# openSX70_MEROE_V7_20190603.net
KiCad netlist of a schematic drawn in EAGLE
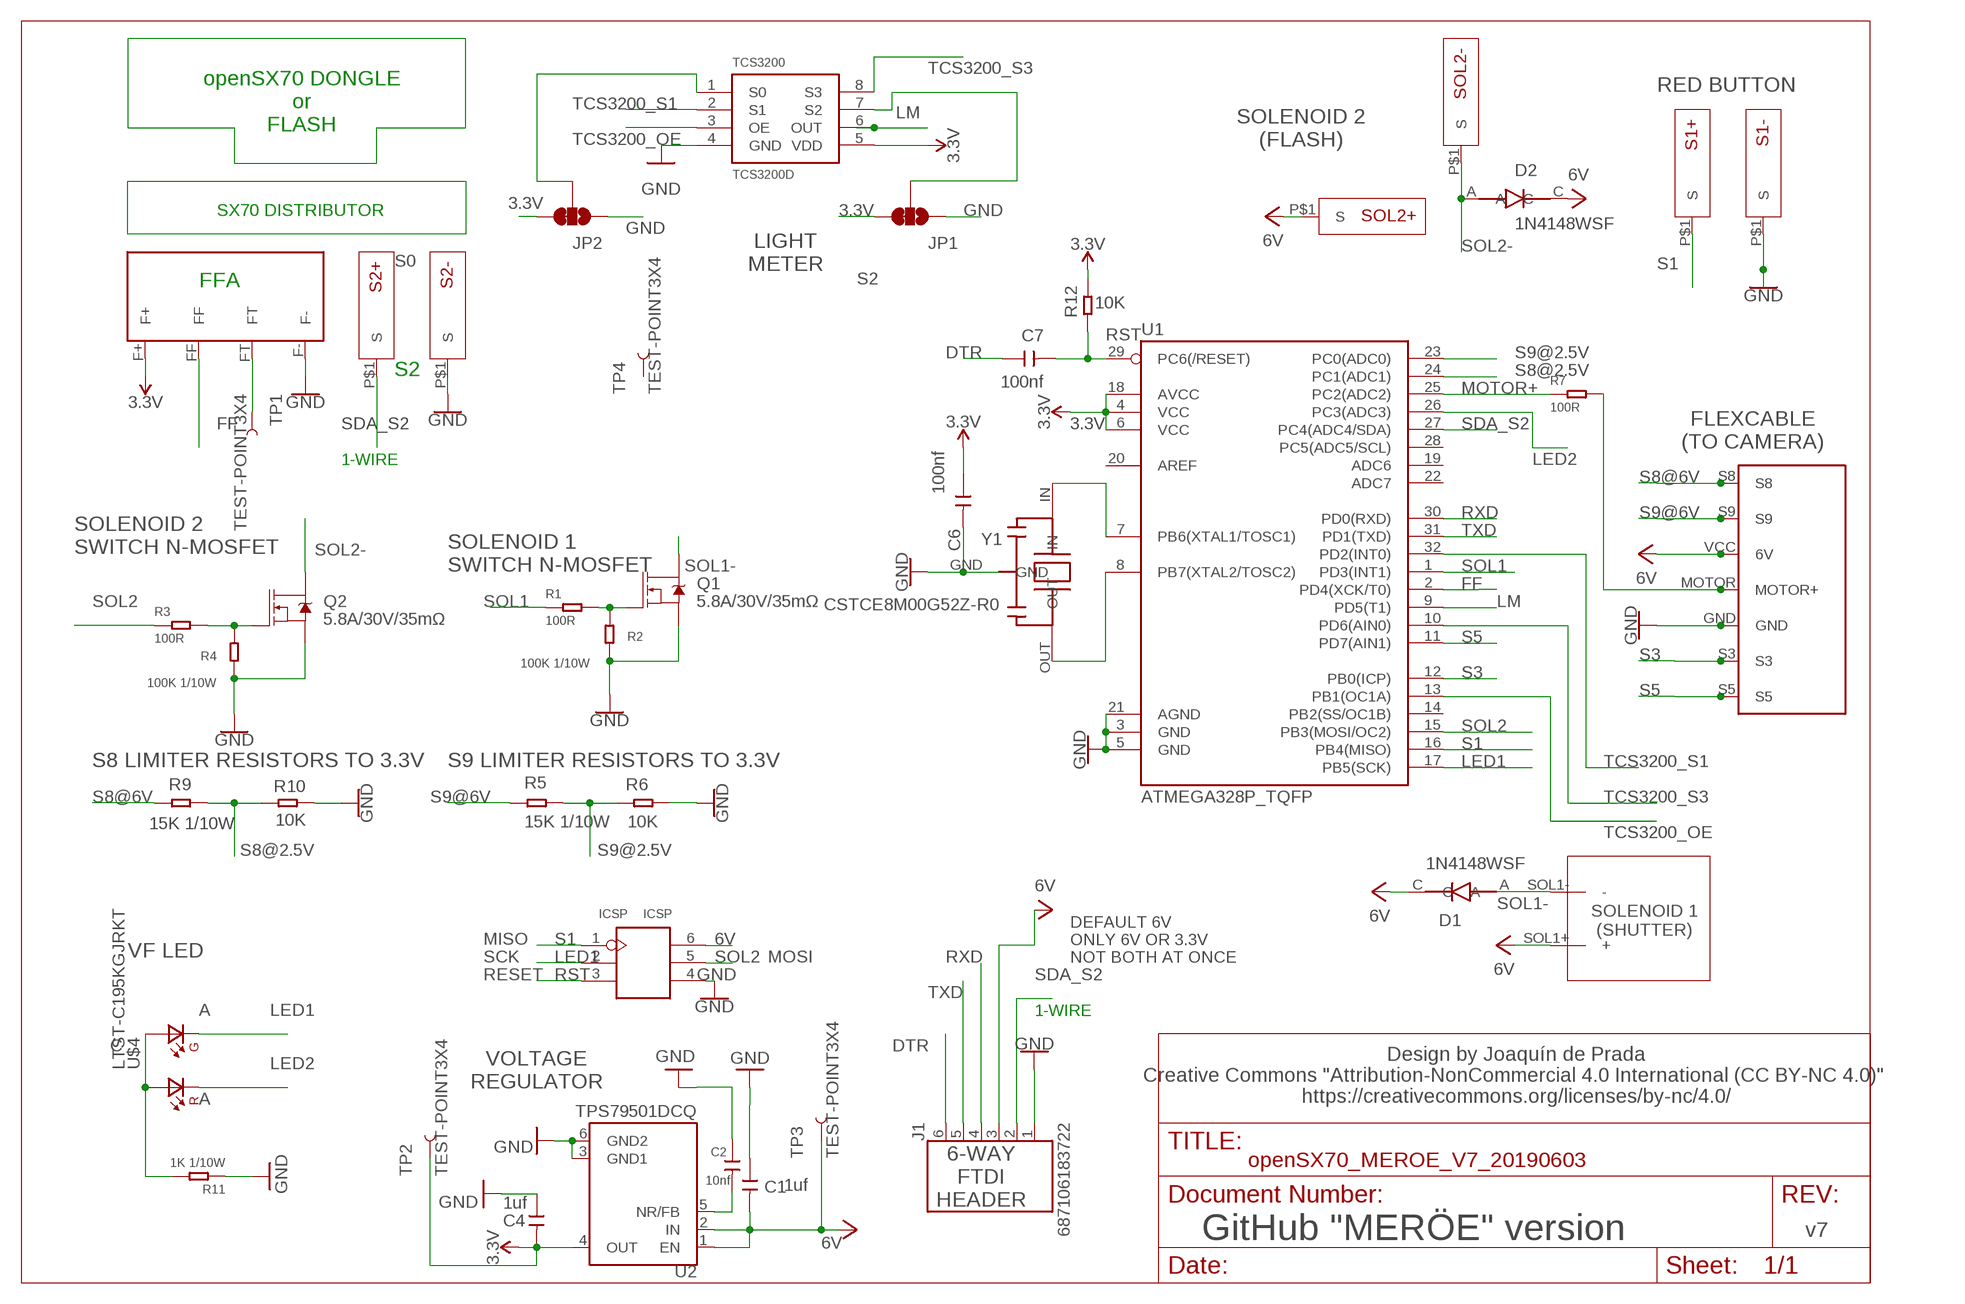
[diagram p0: schematic, sheet 1]

(export (version "E")
  (design (tool "Eeschema 10.0.6"))
  (components
    (comp (ref "C1")
      (value "1uf")
      (footprint "eagle-import:C0603")
      (fields (field (name "MPN") "CC0603KRX5R6BB106"))
      (libsource (lib "eagle-import") (part "CERAMIC-10UF-10V-10%-X5R(0603)"))
    )
    (comp (ref "C2")
      (value "10nf")
      (footprint "eagle-import:C0603")
      (fields (field (name "MPN") "CC0603KRX7R9BB104"))
      (libsource (lib "eagle-import") (part "CERAMIC-100NF-50V-10%-X7R(0603)"))
    )
    (comp (ref "C4")
      (value "1uf")
      (footprint "eagle-import:C0603")
      (fields (field (name "MPN") "CC0603KRX5R6BB106"))
      (libsource (lib "eagle-import") (part "CERAMIC-10UF-10V-10%-X5R(0603)"))
    )
    (comp (ref "C6")
      (value "100nf")
      (footprint "eagle-import:C0603")
      (fields (field (name "MPN") "CC0603KRX7R9BB104"))
      (libsource (lib "eagle-import") (part "CERAMIC-100NF-50V-10%-X7R(0603)"))
    )
    (comp (ref "C7")
      (value "100nf")
      (footprint "eagle-import:C0603")
      (fields (field (name "MPN") "CC0603KRX7R9BB104"))
      (libsource (lib "eagle-import") (part "CERAMIC-100NF-50V-10%-X7R(0603)"))
    )
    (comp (ref "D1")
      (value "1N4148WSF")
      (footprint "eagle-import:SODFL2512X100N")
      (fields (field (name "MANUFACTURER") "Fairchild Semiconductor"))
      (libsource (lib "eagle-import") (part "1N4148WS"))
    )
    (comp (ref "D2")
      (value "1N4148WSF")
      (footprint "eagle-import:SODFL2512X100N")
      (fields (field (name "MANUFACTURER") "Fairchild Semiconductor"))
      (libsource (lib "eagle-import") (part "1N4148WS"))
    )
    (comp (ref "ICSP")
      (value "ICSP")
      (footprint "eagle-import:H2X3-2.54")
      (libsource (lib "eagle-import") (part "ICSP"))
    )
    (comp (ref "J1")
      (value "687106183722")
      (footprint "eagle-import:687106183722")
      (fields (field (name "MF") "Wurth Electronics"))
      (libsource (lib "eagle-import") (part "687106183722"))
    )
    (comp (ref "JP1")
      (value "S2")
      (footprint "eagle-import:SMT-JUMPER_3_1-NC_TRACE_SILK")
      (libsource (lib "eagle-import") (part "JUMPER-SMT_3_1-NC_TRACE_SILK"))
    )
    (comp (ref "JP2")
      (value "S0")
      (footprint "eagle-import:SMT-JUMPER_3_1-NC_TRACE_SILK")
      (libsource (lib "eagle-import") (part "JUMPER-SMT_3_1-NC_TRACE_SILK"))
    )
    (comp (ref "Q1")
      (value "5.8A/30V/35mΩ")
      (footprint "eagle-import:SOT23-3")
      (libsource (lib "eagle-import") (part "MOSFET-NCH-AO3404A"))
    )
    (comp (ref "Q2")
      (value "5.8A/30V/35mΩ")
      (footprint "eagle-import:SOT23-3")
      (libsource (lib "eagle-import") (part "MOSFET-NCH-AO3404A"))
    )
    (comp (ref "R1")
      (value "100R")
      (footprint "eagle-import:R0603")
      (fields (field (name "MPN") "RC0603JR-07100RL"))
      (libsource (lib "eagle-import") (part "SMD-RES-100R-5%-1/10W(0603)"))
    )
    (comp (ref "R2")
      (value "100K 1/10W")
      (footprint "eagle-import:R0603")
      (fields (field (name "MPN") "RC0603JR-07100KL"))
      (libsource (lib "eagle-import") (part "SMD-RES-100K-5%-1/10W(0603)"))
    )
    (comp (ref "R3")
      (value "100R")
      (footprint "eagle-import:R0603")
      (fields (field (name "MPN") "RC0603JR-07100RL"))
      (libsource (lib "eagle-import") (part "SMD-RES-100R-5%-1/10W(0603)"))
    )
    (comp (ref "R4")
      (value "100K 1/10W")
      (footprint "eagle-import:R0603")
      (fields (field (name "MPN") "RC0603JR-07100KL"))
      (libsource (lib "eagle-import") (part "SMD-RES-100K-5%-1/10W(0603)"))
    )
    (comp (ref "R5")
      (value "15K 1/10W")
      (footprint "eagle-import:R0603")
      (fields (field (name "MPN") "RC0603FR-0715KL"))
      (libsource (lib "eagle-import") (part "SMD-RES-15K-1%-1/10W(0603)"))
    )
    (comp (ref "R6")
      (value "10K")
      (footprint "eagle-import:R0603")
      (fields (field (name "MPN") "RC0603FR-0710KL"))
      (libsource (lib "eagle-import") (part "SMD-RES-10K-1%-1/10W(0603)"))
    )
    (comp (ref "R7")
      (value "100R")
      (footprint "eagle-import:R0603")
      (fields (field (name "MPN") "RC0603JR-07100RL"))
      (libsource (lib "eagle-import") (part "SMD-RES-100R-5%-1/10W(0603)"))
    )
    (comp (ref "R9")
      (value "15K 1/10W")
      (footprint "eagle-import:R0603")
      (fields (field (name "MPN") "RC0603FR-0715KL"))
      (libsource (lib "eagle-import") (part "SMD-RES-15K-1%-1/10W(0603)"))
    )
    (comp (ref "R10")
      (value "10K")
      (footprint "eagle-import:R0603")
      (fields (field (name "MPN") "RC0603FR-0710KL"))
      (libsource (lib "eagle-import") (part "SMD-RES-10K-1%-1/10W(0603)"))
    )
    (comp (ref "R11")
      (value "1K 1/10W")
      (footprint "eagle-import:R0603")
      (fields (field (name "MPN") "RC0603JR-071KL"))
      (libsource (lib "eagle-import") (part "SMD-RES-1K-5%-1/10W(0603)"))
    )
    (comp (ref "R12")
      (value "10K")
      (footprint "eagle-import:R0603")
      (fields (field (name "MPN") "RC0603FR-0710KL"))
      (libsource (lib "eagle-import") (part "SMD-RES-10K-1%-1/10W(0603)"))
    )
    (comp (ref "S1+")
      (value "SX70-S-PAD-NEW")
      (footprint "eagle-import:SX70-S-PAD2")
      (libsource (lib "eagle-import") (part "SX70-S-PAD-NEW"))
    )
    (comp (ref "S1-")
      (value "SX70-S-PAD-NEW")
      (footprint "eagle-import:SX70-S-PAD2")
      (libsource (lib "eagle-import") (part "SX70-S-PAD-NEW"))
    )
    (comp (ref "S2+")
      (value "SX70-S-PAD-NEW")
      (footprint "eagle-import:SX70-S-PAD2")
      (libsource (lib "eagle-import") (part "SX70-S-PAD-NEW"))
    )
    (comp (ref "S2-")
      (value "SX70-S-PAD-NEW")
      (footprint "eagle-import:SX70-S-PAD2")
      (libsource (lib "eagle-import") (part "SX70-S-PAD-NEW"))
    )
    (comp (ref "SOL1")
      (value "SX70-SOLENOID1-2PADS")
      (footprint "eagle-import:SX70-SOLENOID1-2")
      (libsource (lib "eagle-import") (part "SX70-SOLENOID1-2PADS"))
    )
    (comp (ref "SOL2+")
      (value "SX70-S-PAD-NEW")
      (footprint "eagle-import:SX70-S-PAD2")
      (libsource (lib "eagle-import") (part "SX70-S-PAD-NEW"))
    )
    (comp (ref "SOL2-")
      (value "SX70-S-PAD-NEW")
      (footprint "eagle-import:SX70-S-PAD2")
      (libsource (lib "eagle-import") (part "SX70-S-PAD-NEW"))
    )
    (comp (ref "TCS3200")
      (value "TCS3200D")
      (footprint "eagle-import:SOIC8")
      (fields (field (name "MF") "ams") (field (name "MP") "TCS3200D-TR"))
      (libsource (lib "eagle-import") (part "TCS3200D"))
    )
    (comp (ref "TP1")
      (value "TEST-POINT3X4")
      (footprint "eagle-import:PAD.03X.04")
      (libsource (lib "eagle-import") (part "TEST-POINT3X4"))
    )
    (comp (ref "TP2")
      (value "TEST-POINT3X4")
      (footprint "eagle-import:PAD.03X.04")
      (libsource (lib "eagle-import") (part "TEST-POINT3X4"))
    )
    (comp (ref "TP3")
      (value "TEST-POINT3X4")
      (footprint "eagle-import:PAD.03X.04")
      (libsource (lib "eagle-import") (part "TEST-POINT3X4"))
    )
    (comp (ref "TP4")
      (value "TEST-POINT3X4")
      (footprint "eagle-import:PAD.03X.04")
      (libsource (lib "eagle-import") (part "TEST-POINT3X4"))
    )
    (comp (ref "U$1")
      (value "SX70-7-PAD")
      (footprint "eagle-import:SX70-7-PAD-PROPER")
      (libsource (lib "eagle-import") (part "SX70-7-PAD"))
    )
    (comp (ref "U$2")
      (value "FFA")
      (footprint "eagle-import:FFA-PAD-PACKAGE")
      (libsource (lib "eagle-import") (part "SX70-FFA-PAD"))
    )
    (comp (ref "U$4")
      (value "LTST-C195KGJRKT")
      (footprint "eagle-import:LTST-BILED-15X16")
      (fields (field (name "MF") "Lite-On Inc."))
      (libsource (lib "eagle-import") (part "LTST-C195KGJRKT"))
    )
    (comp (ref "U1")
      (value "ATMEGA328P_TQFP")
      (footprint "eagle-import:TQFP32-08")
      (libsource (lib "eagle-import") (part "ATMEGA328P_TQFP"))
    )
    (comp (ref "U2")
      (value "TPS79501DCQ")
      (footprint "eagle-import:SOT127P706X180-6N")
      (fields (field (name "MF") "Texas Instruments"))
      (libsource (lib "eagle-import") (part "TPS79501DCQ"))
    )
    (comp (ref "Y1")
      (value "CSTCE8M00G52Z-R0")
      (footprint "eagle-import:CFP95P160X100-3N")
      (fields (field (name "MF") "Murata") (field (name "MP") "CSTCE16M0V53-R0"))
      (libsource (lib "eagle-import") (part "CSTCE16M0V53-R0"))
    )
  )
  (nets
    (net (code "1") (name "/DTR") (class "Default")
      (node (ref "C7") (pin "1") (pinfunction "1_1") (pintype "passive"))
      (node (ref "J1") (pin "6") (pinfunction "1_6") (pintype "passive"))
    )
    (net (code "2") (name "/FF") (class "Default")
      (node (ref "U$2") (pin "FF") (pinfunction "FF_FF") (pintype "bidirectional"))
      (node (ref "U1") (pin "2") (pinfunction "PD4(XCK/T0)_2") (pintype "bidirectional"))
    )
    (net (code "3") (name "/LED1") (class "Default")
      (node (ref "ICSP") (pin "2") (pinfunction "SCK_2") (pintype "bidirectional"))
      (node (ref "U$4") (pin "P$3") (pinfunction "K1_P$3") (pintype "passive"))
      (node (ref "U1") (pin "17") (pinfunction "PB5(SCK)_17") (pintype "bidirectional"))
    )
    (net (code "4") (name "/LED2") (class "Default")
      (node (ref "U$4") (pin "P$4") (pinfunction "K2_P$4") (pintype "passive"))
      (node (ref "U1") (pin "26") (pinfunction "PC3(ADC3)_26") (pintype "bidirectional"))
    )
    (net (code "5") (name "/LM") (class "Default")
      (node (ref "TCS3200") (pin "6") (pinfunction "OUT_6") (pintype "bidirectional"))
      (node (ref "U1") (pin "9") (pinfunction "PD5(T1)_9") (pintype "bidirectional"))
    )
    (net (code "6") (name "/MOTOR+") (class "Default")
      (node (ref "R7") (pin "1") (pinfunction "1_1") (pintype "passive"))
      (node (ref "U1") (pin "25") (pinfunction "PC2(ADC2)_25") (pintype "bidirectional"))
    )
    (net (code "7") (name "/RST") (class "Default")
      (node (ref "C7") (pin "2") (pinfunction "2_2") (pintype "passive"))
      (node (ref "ICSP") (pin "3") (pinfunction "RST_3") (pintype "bidirectional"))
      (node (ref "R12") (pin "1") (pinfunction "1_1") (pintype "passive"))
      (node (ref "U1") (pin "29") (pinfunction "PC6(/RESET)_29") (pintype "bidirectional"))
    )
    (net (code "8") (name "/RXD") (class "Default")
      (node (ref "J1") (pin "4") (pinfunction "3_4") (pintype "passive"))
      (node (ref "U1") (pin "30") (pinfunction "PD0(RXD)_30") (pintype "bidirectional"))
    )
    (net (code "9") (name "/S1") (class "Default")
      (node (ref "ICSP") (pin "1") (pinfunction "MISO_1") (pintype "bidirectional"))
      (node (ref "S1+") (pin "P$1") (pinfunction "S_P$1") (pintype "bidirectional"))
      (node (ref "U1") (pin "16") (pinfunction "PB4(MISO)_16") (pintype "bidirectional"))
    )
    (net (code "10") (name "/S3") (class "Default")
      (node (ref "U$1") (pin "S3") (pinfunction "S3_S3") (pintype "bidirectional"))
      (node (ref "U1") (pin "12") (pinfunction "PB0(ICP)_12") (pintype "bidirectional"))
    )
    (net (code "11") (name "/S5") (class "Default")
      (node (ref "U$1") (pin "S5") (pinfunction "S5_S5") (pintype "bidirectional"))
      (node (ref "U1") (pin "11") (pinfunction "PD7(AIN1)_11") (pintype "bidirectional"))
    )
    (net (code "12") (name "/S8@2.5V") (class "Default")
      (node (ref "R10") (pin "1") (pinfunction "1_1") (pintype "passive"))
      (node (ref "R9") (pin "2") (pinfunction "2_2") (pintype "passive"))
      (node (ref "U1") (pin "24") (pinfunction "PC1(ADC1)_24") (pintype "bidirectional"))
    )
    (net (code "13") (name "/S8@6V") (class "Default")
      (node (ref "R9") (pin "1") (pinfunction "1_1") (pintype "passive"))
      (node (ref "U$1") (pin "S8") (pinfunction "S8_S8") (pintype "bidirectional"))
    )
    (net (code "14") (name "/S9@2.5V") (class "Default")
      (node (ref "R5") (pin "2") (pinfunction "2_2") (pintype "passive"))
      (node (ref "R6") (pin "1") (pinfunction "1_1") (pintype "passive"))
      (node (ref "U1") (pin "23") (pinfunction "PC0(ADC0)_23") (pintype "bidirectional"))
    )
    (net (code "15") (name "/S9@6V") (class "Default")
      (node (ref "R5") (pin "1") (pinfunction "1_1") (pintype "passive"))
      (node (ref "U$1") (pin "S9") (pinfunction "S9_S9") (pintype "bidirectional"))
    )
    (net (code "16") (name "/SDA_S2") (class "Default")
      (node (ref "J1") (pin "2") (pinfunction "5_2") (pintype "passive"))
      (node (ref "S2+") (pin "P$1") (pinfunction "S_P$1") (pintype "bidirectional"))
      (node (ref "U1") (pin "27") (pinfunction "PC4(ADC4/SDA)_27") (pintype "bidirectional"))
    )
    (net (code "17") (name "/SOL1") (class "Default")
      (node (ref "R1") (pin "1") (pinfunction "1_1") (pintype "passive"))
      (node (ref "U1") (pin "1") (pinfunction "PD3(INT1)_1") (pintype "bidirectional"))
    )
    (net (code "18") (name "/SOL1-") (class "Default")
      (node (ref "D1") (pin "A") (pinfunction "A_A") (pintype "passive"))
      (node (ref "Q1") (pin "3") (pinfunction "D_3") (pintype "bidirectional"))
      (node (ref "SOL1") (pin "SOL1-") (pinfunction "-_SOL1-") (pintype "bidirectional"))
    )
    (net (code "19") (name "/SOL2") (class "Default")
      (node (ref "ICSP") (pin "5") (pinfunction "MOSI_5") (pintype "bidirectional"))
      (node (ref "R3") (pin "1") (pinfunction "1_1") (pintype "passive"))
      (node (ref "U1") (pin "15") (pinfunction "PB3(MOSI/OC2)_15") (pintype "bidirectional"))
    )
    (net (code "20") (name "/SOL2-") (class "Default")
      (node (ref "D2") (pin "A") (pinfunction "A_A") (pintype "passive"))
      (node (ref "Q2") (pin "3") (pinfunction "D_3") (pintype "bidirectional"))
      (node (ref "SOL2-") (pin "P$1") (pinfunction "S_P$1") (pintype "bidirectional"))
    )
    (net (code "21") (name "/TCS3200_OE") (class "Default")
      (node (ref "TCS3200") (pin "3") (pinfunction "OE_3") (pintype "bidirectional"))
      (node (ref "U1") (pin "13") (pinfunction "PB1(OC1A)_13") (pintype "bidirectional"))
    )
    (net (code "22") (name "/TCS3200_S1") (class "Default")
      (node (ref "TCS3200") (pin "2") (pinfunction "S1_2") (pintype "bidirectional"))
      (node (ref "U1") (pin "32") (pinfunction "PD2(INT0)_32") (pintype "bidirectional"))
    )
    (net (code "23") (name "/TCS3200_S3") (class "Default")
      (node (ref "TCS3200") (pin "8") (pinfunction "S3_8") (pintype "bidirectional"))
      (node (ref "U1") (pin "10") (pinfunction "PD6(AIN0)_10") (pintype "bidirectional"))
    )
    (net (code "24") (name "/TXD") (class "Default")
      (node (ref "J1") (pin "5") (pinfunction "2_5") (pintype "passive"))
      (node (ref "U1") (pin "31") (pinfunction "PD1(TXD)_31") (pintype "bidirectional"))
    )
    (net (code "25") (name "3.3V") (class "Default")
      (node (ref "C4") (pin "2") (pinfunction "2_2") (pintype "passive"))
      (node (ref "C6") (pin "1") (pinfunction "1_1") (pintype "passive"))
      (node (ref "JP1") (pin "3") (pinfunction "3_3") (pintype "passive"))
      (node (ref "JP2") (pin "3") (pinfunction "3_3") (pintype "passive"))
      (node (ref "R12") (pin "2") (pinfunction "2_2") (pintype "passive"))
      (node (ref "TCS3200") (pin "5") (pinfunction "VDD_5") (pintype "bidirectional"))
      (node (ref "TP2") (pin "P$1") (pinfunction "1_P$1") (pintype "bidirectional"))
      (node (ref "U$2") (pin "F+") (pinfunction "F+_F+") (pintype "bidirectional"))
      (node (ref "U1") (pin "18") (pinfunction "AVCC_18") (pintype "bidirectional"))
      (node (ref "U1") (pin "4") (pinfunction "VCC_4") (pintype "bidirectional"))
      (node (ref "U1") (pin "6") (pinfunction "VCC_6") (pintype "bidirectional"))
      (node (ref "U2") (pin "4") (pinfunction "OUT_4") (pintype "output"))
    )
    (net (code "26") (name "6V") (class "Default")
      (node (ref "C1") (pin "2") (pinfunction "2_2") (pintype "passive"))
      (node (ref "D1") (pin "C") (pinfunction "C_C") (pintype "passive"))
      (node (ref "D2") (pin "C") (pinfunction "C_C") (pintype "passive"))
      (node (ref "ICSP") (pin "6") (pinfunction "VCC_6") (pintype "bidirectional"))
      (node (ref "J1") (pin "3") (pinfunction "4_3") (pintype "passive"))
      (node (ref "SOL1") (pin "SOL1+") (pinfunction "+_SOL1+") (pintype "bidirectional"))
      (node (ref "SOL2+") (pin "P$1") (pinfunction "S_P$1") (pintype "bidirectional"))
      (node (ref "TP3") (pin "P$1") (pinfunction "1_P$1") (pintype "bidirectional"))
      (node (ref "U$1") (pin "VCC") (pinfunction "6V_VCC") (pintype "bidirectional"))
      (node (ref "U2") (pin "1") (pinfunction "EN_1") (pintype "input"))
      (node (ref "U2") (pin "2") (pinfunction "IN_2") (pintype "input"))
    )
    (net (code "27") (name "GND") (class "Default")
      (node (ref "C1") (pin "1") (pinfunction "1_1") (pintype "passive"))
      (node (ref "C2") (pin "1") (pinfunction "1_1") (pintype "passive"))
      (node (ref "C4") (pin "1") (pinfunction "1_1") (pintype "passive"))
      (node (ref "C6") (pin "2") (pinfunction "2_2") (pintype "passive"))
      (node (ref "ICSP") (pin "4") (pinfunction "GND_4") (pintype "bidirectional"))
      (node (ref "J1") (pin "1") (pinfunction "6_1") (pintype "passive"))
      (node (ref "JP1") (pin "1") (pinfunction "1_1") (pintype "passive"))
      (node (ref "JP2") (pin "1") (pinfunction "1_1") (pintype "passive"))
      (node (ref "Q1") (pin "2") (pinfunction "S_2") (pintype "bidirectional"))
      (node (ref "Q2") (pin "2") (pinfunction "S_2") (pintype "bidirectional"))
      (node (ref "R10") (pin "2") (pinfunction "2_2") (pintype "passive"))
      (node (ref "R11") (pin "1") (pinfunction "1_1") (pintype "passive"))
      (node (ref "R2") (pin "1") (pinfunction "1_1") (pintype "passive"))
      (node (ref "R4") (pin "1") (pinfunction "1_1") (pintype "passive"))
      (node (ref "R6") (pin "2") (pinfunction "2_2") (pintype "passive"))
      (node (ref "S1-") (pin "P$1") (pinfunction "S_P$1") (pintype "bidirectional"))
      (node (ref "S2-") (pin "P$1") (pinfunction "S_P$1") (pintype "bidirectional"))
      (node (ref "TCS3200") (pin "4") (pinfunction "GND_4") (pintype "bidirectional"))
      (node (ref "U$1") (pin "GND") (pinfunction "GND_GND") (pintype "bidirectional"))
      (node (ref "U$2") (pin "F-") (pinfunction "F-_F-") (pintype "bidirectional"))
      (node (ref "U1") (pin "21") (pinfunction "AGND_21") (pintype "bidirectional"))
      (node (ref "U1") (pin "3") (pinfunction "GND_3") (pintype "bidirectional"))
      (node (ref "U1") (pin "5") (pinfunction "GND_5") (pintype "bidirectional"))
      (node (ref "U2") (pin "3") (pinfunction "GND1_3") (pintype "power_in"))
      (node (ref "U2") (pin "6") (pinfunction "GND2_6") (pintype "power_in"))
      (node (ref "Y1") (pin "GND") (pinfunction "GND_GND") (pintype "passive"))
    )
    (net (code "28") (name "Net-(Q1-G)") (class "Default")
      (node (ref "Q1") (pin "1") (pinfunction "G_1") (pintype "bidirectional"))
      (node (ref "R1") (pin "2") (pinfunction "2_2") (pintype "passive"))
      (node (ref "R2") (pin "2") (pinfunction "2_2") (pintype "passive"))
    )
    (net (code "29") (name "Net-(Q2-G)") (class "Default")
      (node (ref "Q2") (pin "1") (pinfunction "G_1") (pintype "bidirectional"))
      (node (ref "R3") (pin "2") (pinfunction "2_2") (pintype "passive"))
      (node (ref "R4") (pin "2") (pinfunction "2_2") (pintype "passive"))
    )
    (net (code "30") (name "Net-(TCS3200-S0)") (class "Default")
      (node (ref "JP2") (pin "2") (pinfunction "2_2") (pintype "passive"))
      (node (ref "TCS3200") (pin "1") (pinfunction "S0_1") (pintype "bidirectional"))
    )
    (net (code "31") (name "Net-(TCS3200-S2)") (class "Default")
      (node (ref "JP1") (pin "2") (pinfunction "2_2") (pintype "passive"))
      (node (ref "TCS3200") (pin "7") (pinfunction "S2_7") (pintype "bidirectional"))
    )
    (net (code "32") (name "Net-(TP1-1)") (class "Default")
      (node (ref "TP1") (pin "P$1") (pinfunction "1_P$1") (pintype "bidirectional"))
      (node (ref "U$2") (pin "FT") (pinfunction "FT_FT") (pintype "bidirectional"))
    )
    (net (code "33") (name "Net-(U$1-MOTOR+)") (class "Default")
      (node (ref "R7") (pin "2") (pinfunction "2_2") (pintype "passive"))
      (node (ref "U$1") (pin "MOTOR") (pinfunction "MOTOR+_MOTOR") (pintype "bidirectional"))
    )
    (net (code "34") (name "Net-(U$4-A1)") (class "Default")
      (node (ref "R11") (pin "2") (pinfunction "2_2") (pintype "passive"))
      (node (ref "U$4") (pin "P$1") (pinfunction "A1_P$1") (pintype "passive"))
      (node (ref "U$4") (pin "P$2") (pinfunction "A2_P$2") (pintype "passive"))
    )
    (net (code "35") (name "Net-(U1-PB6(XTAL1{slash}TOSC1))") (class "Default")
      (node (ref "U1") (pin "7") (pinfunction "PB6(XTAL1/TOSC1)_7") (pintype "bidirectional"))
      (node (ref "Y1") (pin "IN") (pinfunction "IN_IN") (pintype "input"))
    )
    (net (code "36") (name "Net-(U1-PB7(XTAL2{slash}TOSC2))") (class "Default")
      (node (ref "U1") (pin "8") (pinfunction "PB7(XTAL2/TOSC2)_8") (pintype "bidirectional"))
      (node (ref "Y1") (pin "OUT") (pinfunction "OUT_OUT") (pintype "output"))
    )
    (net (code "37") (name "Net-(U2-NR{slash}FB)") (class "Default")
      (node (ref "C2") (pin "2") (pinfunction "2_2") (pintype "passive"))
      (node (ref "U2") (pin "5") (pinfunction "NR/FB_5") (pintype "input"))
    )
    (net (code "38") (name "unconnected-(TP4-1-PadP$1)") (class "Default")
      (node (ref "TP4") (pin "P$1") (pinfunction "1_P$1") (pintype "bidirectional"))
    )
    (net (code "39") (name "unconnected-(U1-ADC6-Pad19)") (class "Default")
      (node (ref "U1") (pin "19") (pinfunction "ADC6_19") (pintype "bidirectional"))
    )
    (net (code "40") (name "unconnected-(U1-ADC7-Pad22)") (class "Default")
      (node (ref "U1") (pin "22") (pinfunction "ADC7_22") (pintype "bidirectional"))
    )
    (net (code "41") (name "unconnected-(U1-AREF-Pad20)") (class "Default")
      (node (ref "U1") (pin "20") (pinfunction "AREF_20") (pintype "bidirectional"))
    )
    (net (code "42") (name "unconnected-(U1-PB2(SS{slash}OC1B)-Pad14)") (class "Default")
      (node (ref "U1") (pin "14") (pinfunction "PB2(SS/OC1B)_14") (pintype "bidirectional"))
    )
    (net (code "43") (name "unconnected-(U1-PC5(ADC5{slash}SCL)-Pad28)") (class "Default")
      (node (ref "U1") (pin "28") (pinfunction "PC5(ADC5/SCL)_28") (pintype "bidirectional"))
    )
  )
)
